# SODIMM.net
KiCad netlist of a schematic drawn in Altium Designer
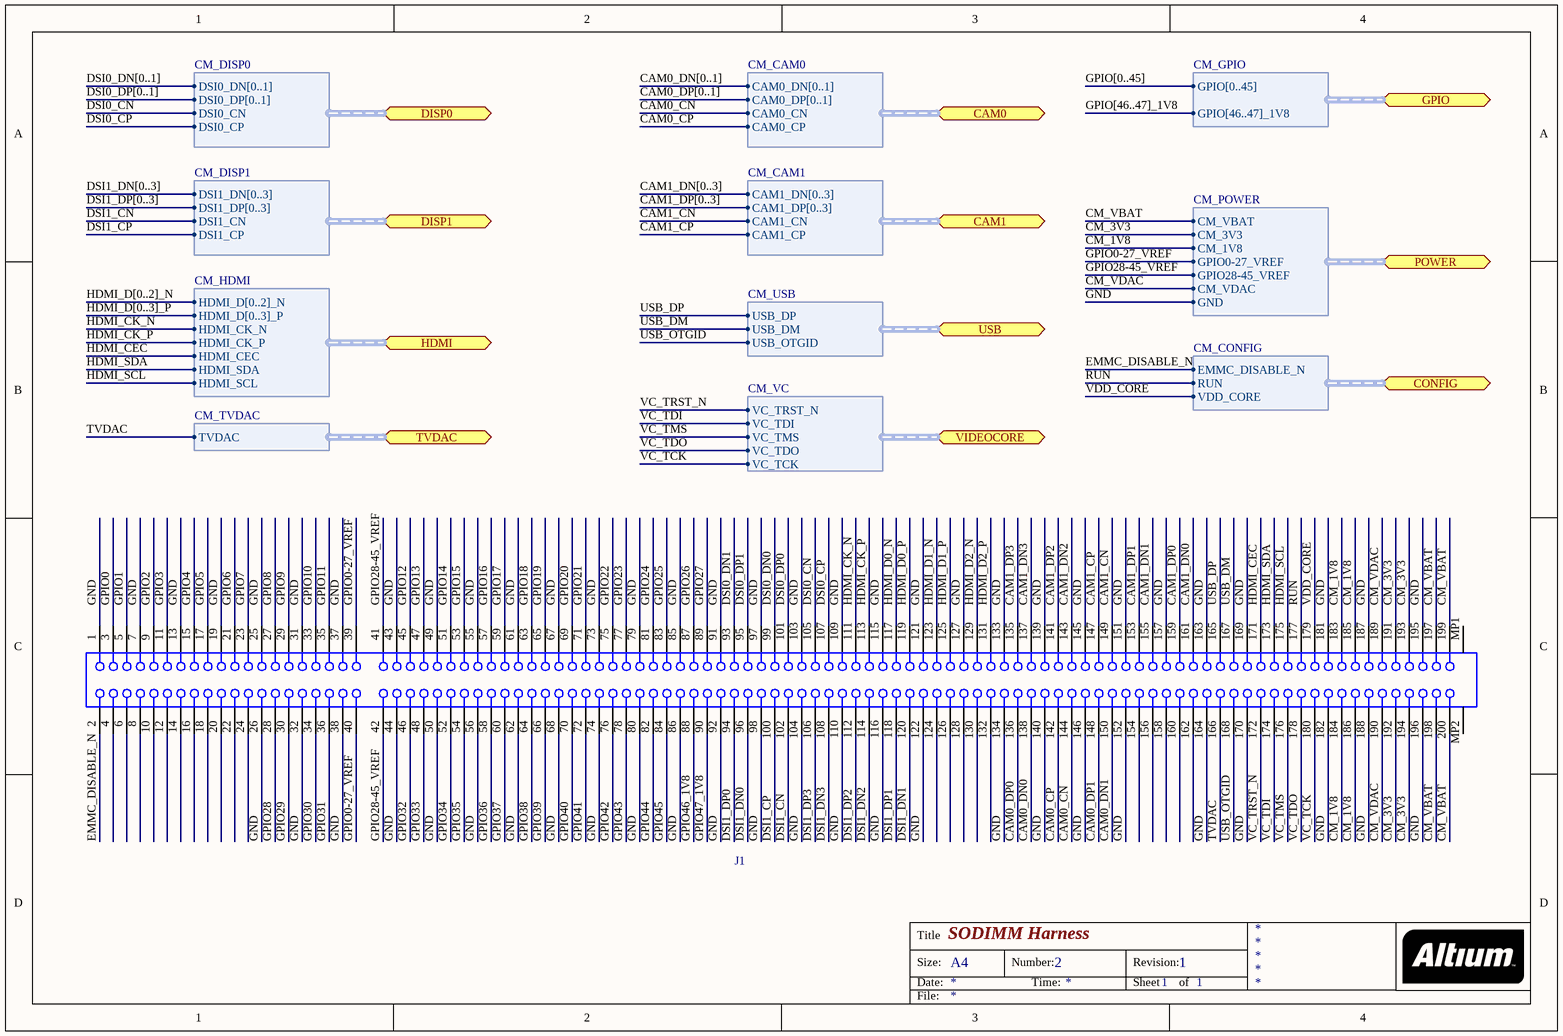
[diagram p0: SODIMM.SchDoc]

(export (version "E")
  (design (tool "Eeschema 10.0.6"))
  (components
    (comp (ref "J1")
      (value "~")
      (footprint "BTB-SM0-6-2V200")
      (description "Board-to-Board Connector, SMT, Vertical, Pitch 0.6mm, 200-Position")
      (fields (field (name "PUBLISHER") "Altium"))
      (libsource (lib "Altium Shanghai") (part "CMP-0001-00111-1"))
    )
  )
  (nets
    (net (code "15") (name "/CAM0_CN") (class "Default")
      (node (ref "J1") (pin "144") (pinfunction "144_144") (pintype "passive"))
    )
    (net (code "16") (name "/CAM0_CP") (class "Default")
      (node (ref "J1") (pin "142") (pinfunction "142_142") (pintype "passive"))
    )
    (net (code "17") (name "/CAM0_DN0") (class "Default")
      (node (ref "J1") (pin "138") (pinfunction "138_138") (pintype "passive"))
    )
    (net (code "18") (name "/CAM0_DN1") (class "Default")
      (node (ref "J1") (pin "150") (pinfunction "150_150") (pintype "passive"))
    )
    (net (code "20") (name "/CAM0_DP0") (class "Default")
      (node (ref "J1") (pin "136") (pinfunction "136_136") (pintype "passive"))
    )
    (net (code "21") (name "/CAM0_DP1") (class "Default")
      (node (ref "J1") (pin "148") (pinfunction "148_148") (pintype "passive"))
    )
    (net (code "23") (name "/CAM1_CN") (class "Default")
      (node (ref "J1") (pin "149") (pinfunction "149_149") (pintype "passive"))
    )
    (net (code "24") (name "/CAM1_CP") (class "Default")
      (node (ref "J1") (pin "147") (pinfunction "147_147") (pintype "passive"))
    )
    (net (code "25") (name "/CAM1_DN0") (class "Default")
      (node (ref "J1") (pin "161") (pinfunction "161_161") (pintype "passive"))
    )
    (net (code "26") (name "/CAM1_DN1") (class "Default")
      (node (ref "J1") (pin "155") (pinfunction "155_155") (pintype "passive"))
    )
    (net (code "27") (name "/CAM1_DN2") (class "Default")
      (node (ref "J1") (pin "143") (pinfunction "143_143") (pintype "passive"))
    )
    (net (code "28") (name "/CAM1_DN3") (class "Default")
      (node (ref "J1") (pin "137") (pinfunction "137_137") (pintype "passive"))
    )
    (net (code "30") (name "/CAM1_DP0") (class "Default")
      (node (ref "J1") (pin "159") (pinfunction "159_159") (pintype "passive"))
    )
    (net (code "31") (name "/CAM1_DP1") (class "Default")
      (node (ref "J1") (pin "153") (pinfunction "153_153") (pintype "passive"))
    )
    (net (code "32") (name "/CAM1_DP2") (class "Default")
      (node (ref "J1") (pin "141") (pinfunction "141_141") (pintype "passive"))
    )
    (net (code "33") (name "/CAM1_DP3") (class "Default")
      (node (ref "J1") (pin "135") (pinfunction "135_135") (pintype "passive"))
    )
    (net (code "35") (name "/CM_1V8") (class "Default")
      (node (ref "J1") (pin "183") (pinfunction "183_183") (pintype "passive"))
      (node (ref "J1") (pin "184") (pinfunction "184_184") (pintype "passive"))
      (node (ref "J1") (pin "185") (pinfunction "185_185") (pintype "passive"))
      (node (ref "J1") (pin "186") (pinfunction "186_186") (pintype "passive"))
    )
    (net (code "36") (name "/CM_3V3") (class "Default")
      (node (ref "J1") (pin "191") (pinfunction "191_191") (pintype "passive"))
      (node (ref "J1") (pin "192") (pinfunction "192_192") (pintype "passive"))
      (node (ref "J1") (pin "193") (pinfunction "193_193") (pintype "passive"))
      (node (ref "J1") (pin "194") (pinfunction "194_194") (pintype "passive"))
    )
    (net (code "37") (name "/CM_VBAT") (class "Default")
      (node (ref "J1") (pin "197") (pinfunction "197_197") (pintype "passive"))
      (node (ref "J1") (pin "198") (pinfunction "198_198") (pintype "passive"))
      (node (ref "J1") (pin "199") (pinfunction "199_199") (pintype "passive"))
      (node (ref "J1") (pin "200") (pinfunction "200_200") (pintype "passive"))
    )
    (net (code "38") (name "/CM_VDAC") (class "Default")
      (node (ref "J1") (pin "189") (pinfunction "189_189") (pintype "passive"))
      (node (ref "J1") (pin "190") (pinfunction "190_190") (pintype "passive"))
    )
    (net (code "39") (name "/DSI0_CN") (class "Default")
      (node (ref "J1") (pin "105") (pinfunction "105_105") (pintype "passive"))
    )
    (net (code "40") (name "/DSI0_CP") (class "Default")
      (node (ref "J1") (pin "107") (pinfunction "107_107") (pintype "passive"))
    )
    (net (code "41") (name "/DSI0_DN0") (class "Default")
      (node (ref "J1") (pin "99") (pinfunction "99_99") (pintype "passive"))
    )
    (net (code "42") (name "/DSI0_DN1") (class "Default")
      (node (ref "J1") (pin "93") (pinfunction "93_93") (pintype "passive"))
    )
    (net (code "44") (name "/DSI0_DP0") (class "Default")
      (node (ref "J1") (pin "101") (pinfunction "101_101") (pintype "passive"))
    )
    (net (code "45") (name "/DSI0_DP1") (class "Default")
      (node (ref "J1") (pin "95") (pinfunction "95_95") (pintype "passive"))
    )
    (net (code "47") (name "/DSI1_CN") (class "Default")
      (node (ref "J1") (pin "102") (pinfunction "102_102") (pintype "passive"))
    )
    (net (code "48") (name "/DSI1_CP") (class "Default")
      (node (ref "J1") (pin "100") (pinfunction "100_100") (pintype "passive"))
    )
    (net (code "49") (name "/DSI1_DN0") (class "Default")
      (node (ref "J1") (pin "96") (pinfunction "96_96") (pintype "passive"))
    )
    (net (code "50") (name "/DSI1_DN1") (class "Default")
      (node (ref "J1") (pin "120") (pinfunction "120_120") (pintype "passive"))
    )
    (net (code "51") (name "/DSI1_DN2") (class "Default")
      (node (ref "J1") (pin "114") (pinfunction "114_114") (pintype "passive"))
    )
    (net (code "52") (name "/DSI1_DN3") (class "Default")
      (node (ref "J1") (pin "108") (pinfunction "108_108") (pintype "passive"))
    )
    (net (code "54") (name "/DSI1_DP0") (class "Default")
      (node (ref "J1") (pin "94") (pinfunction "94_94") (pintype "passive"))
    )
    (net (code "55") (name "/DSI1_DP1") (class "Default")
      (node (ref "J1") (pin "118") (pinfunction "118_118") (pintype "passive"))
    )
    (net (code "56") (name "/DSI1_DP2") (class "Default")
      (node (ref "J1") (pin "112") (pinfunction "112_112") (pintype "passive"))
    )
    (net (code "57") (name "/DSI1_DP3") (class "Default")
      (node (ref "J1") (pin "106") (pinfunction "106_106") (pintype "passive"))
    )
    (net (code "59") (name "/EMMC_DISABLE_N") (class "Default")
      (node (ref "J1") (pin "2") (pinfunction "2_2") (pintype "passive"))
    )
    (net (code "60") (name "/GND") (class "Default")
      (node (ref "J1") (pin "1") (pinfunction "1_1") (pintype "passive"))
      (node (ref "J1") (pin "103") (pinfunction "103_103") (pintype "passive"))
      (node (ref "J1") (pin "104") (pinfunction "104_104") (pintype "passive"))
      (node (ref "J1") (pin "109") (pinfunction "109_109") (pintype "passive"))
      (node (ref "J1") (pin "110") (pinfunction "110_110") (pintype "passive"))
      (node (ref "J1") (pin "115") (pinfunction "115_115") (pintype "passive"))
      (node (ref "J1") (pin "116") (pinfunction "116_116") (pintype "passive"))
      (node (ref "J1") (pin "121") (pinfunction "121_121") (pintype "passive"))
      (node (ref "J1") (pin "122") (pinfunction "122_122") (pintype "passive"))
      (node (ref "J1") (pin "127") (pinfunction "127_127") (pintype "passive"))
      (node (ref "J1") (pin "13") (pinfunction "13_13") (pintype "passive"))
      (node (ref "J1") (pin "133") (pinfunction "133_133") (pintype "passive"))
      (node (ref "J1") (pin "134") (pinfunction "134_134") (pintype "passive"))
      (node (ref "J1") (pin "139") (pinfunction "139_139") (pintype "passive"))
      (node (ref "J1") (pin "140") (pinfunction "140_140") (pintype "passive"))
      (node (ref "J1") (pin "145") (pinfunction "145_145") (pintype "passive"))
      (node (ref "J1") (pin "146") (pinfunction "146_146") (pintype "passive"))
      (node (ref "J1") (pin "151") (pinfunction "151_151") (pintype "passive"))
      (node (ref "J1") (pin "152") (pinfunction "152_152") (pintype "passive"))
      (node (ref "J1") (pin "157") (pinfunction "157_157") (pintype "passive"))
      (node (ref "J1") (pin "163") (pinfunction "163_163") (pintype "passive"))
      (node (ref "J1") (pin "164") (pinfunction "164_164") (pintype "passive"))
      (node (ref "J1") (pin "169") (pinfunction "169_169") (pintype "passive"))
      (node (ref "J1") (pin "170") (pinfunction "170_170") (pintype "passive"))
      (node (ref "J1") (pin "181") (pinfunction "181_181") (pintype "passive"))
      (node (ref "J1") (pin "182") (pinfunction "182_182") (pintype "passive"))
      (node (ref "J1") (pin "187") (pinfunction "187_187") (pintype "passive"))
      (node (ref "J1") (pin "188") (pinfunction "188_188") (pintype "passive"))
      (node (ref "J1") (pin "19") (pinfunction "19_19") (pintype "passive"))
      (node (ref "J1") (pin "195") (pinfunction "195_195") (pintype "passive"))
      (node (ref "J1") (pin "196") (pinfunction "196_196") (pintype "passive"))
      (node (ref "J1") (pin "25") (pinfunction "25_25") (pintype "passive"))
      (node (ref "J1") (pin "26") (pinfunction "26_26") (pintype "passive"))
      (node (ref "J1") (pin "31") (pinfunction "31_31") (pintype "passive"))
      (node (ref "J1") (pin "32") (pinfunction "32_32") (pintype "passive"))
      (node (ref "J1") (pin "37") (pinfunction "37_37") (pintype "passive"))
      (node (ref "J1") (pin "38") (pinfunction "38_38") (pintype "passive"))
      (node (ref "J1") (pin "43") (pinfunction "43_43") (pintype "passive"))
      (node (ref "J1") (pin "44") (pinfunction "44_44") (pintype "passive"))
      (node (ref "J1") (pin "49") (pinfunction "49_49") (pintype "passive"))
      (node (ref "J1") (pin "50") (pinfunction "50_50") (pintype "passive"))
      (node (ref "J1") (pin "55") (pinfunction "55_55") (pintype "passive"))
      (node (ref "J1") (pin "56") (pinfunction "56_56") (pintype "passive"))
      (node (ref "J1") (pin "61") (pinfunction "61_61") (pintype "passive"))
      (node (ref "J1") (pin "62") (pinfunction "62_62") (pintype "passive"))
      (node (ref "J1") (pin "67") (pinfunction "67_67") (pintype "passive"))
      (node (ref "J1") (pin "68") (pinfunction "68_68") (pintype "passive"))
      (node (ref "J1") (pin "7") (pinfunction "7_7") (pintype "passive"))
      (node (ref "J1") (pin "73") (pinfunction "73_73") (pintype "passive"))
      (node (ref "J1") (pin "74") (pinfunction "74_74") (pintype "passive"))
      (node (ref "J1") (pin "79") (pinfunction "79_79") (pintype "passive"))
      (node (ref "J1") (pin "80") (pinfunction "80_80") (pintype "passive"))
      (node (ref "J1") (pin "85") (pinfunction "85_85") (pintype "passive"))
      (node (ref "J1") (pin "86") (pinfunction "86_86") (pintype "passive"))
      (node (ref "J1") (pin "91") (pinfunction "91_91") (pintype "passive"))
      (node (ref "J1") (pin "92") (pinfunction "92_92") (pintype "passive"))
      (node (ref "J1") (pin "97") (pinfunction "97_97") (pintype "passive"))
      (node (ref "J1") (pin "98") (pinfunction "98_98") (pintype "passive"))
    )
    (net (code "61") (name "/GPIO0") (class "Default")
      (node (ref "J1") (pin "3") (pinfunction "3_3") (pintype "passive"))
    )
    (net (code "62") (name "/GPIO0-27_VREF") (class "Default")
      (node (ref "J1") (pin "39") (pinfunction "39_39") (pintype "passive"))
      (node (ref "J1") (pin "40") (pinfunction "40_40") (pintype "passive"))
    )
    (net (code "63") (name "/GPIO1") (class "Default")
      (node (ref "J1") (pin "5") (pinfunction "5_5") (pintype "passive"))
    )
    (net (code "64") (name "/GPIO2") (class "Default")
      (node (ref "J1") (pin "9") (pinfunction "9_9") (pintype "passive"))
    )
    (net (code "65") (name "/GPIO3") (class "Default")
      (node (ref "J1") (pin "11") (pinfunction "11_11") (pintype "passive"))
    )
    (net (code "66") (name "/GPIO4") (class "Default")
      (node (ref "J1") (pin "15") (pinfunction "15_15") (pintype "passive"))
    )
    (net (code "67") (name "/GPIO5") (class "Default")
      (node (ref "J1") (pin "17") (pinfunction "17_17") (pintype "passive"))
    )
    (net (code "68") (name "/GPIO6") (class "Default")
      (node (ref "J1") (pin "21") (pinfunction "21_21") (pintype "passive"))
    )
    (net (code "69") (name "/GPIO7") (class "Default")
      (node (ref "J1") (pin "23") (pinfunction "23_23") (pintype "passive"))
    )
    (net (code "70") (name "/GPIO8") (class "Default")
      (node (ref "J1") (pin "27") (pinfunction "27_27") (pintype "passive"))
    )
    (net (code "71") (name "/GPIO9") (class "Default")
      (node (ref "J1") (pin "29") (pinfunction "29_29") (pintype "passive"))
    )
    (net (code "72") (name "/GPIO10") (class "Default")
      (node (ref "J1") (pin "33") (pinfunction "33_33") (pintype "passive"))
    )
    (net (code "73") (name "/GPIO11") (class "Default")
      (node (ref "J1") (pin "35") (pinfunction "35_35") (pintype "passive"))
    )
    (net (code "74") (name "/GPIO12") (class "Default")
      (node (ref "J1") (pin "45") (pinfunction "45_45") (pintype "passive"))
    )
    (net (code "75") (name "/GPIO13") (class "Default")
      (node (ref "J1") (pin "47") (pinfunction "47_47") (pintype "passive"))
    )
    (net (code "76") (name "/GPIO14") (class "Default")
      (node (ref "J1") (pin "51") (pinfunction "51_51") (pintype "passive"))
    )
    (net (code "77") (name "/GPIO15") (class "Default")
      (node (ref "J1") (pin "53") (pinfunction "53_53") (pintype "passive"))
    )
    (net (code "78") (name "/GPIO16") (class "Default")
      (node (ref "J1") (pin "57") (pinfunction "57_57") (pintype "passive"))
    )
    (net (code "79") (name "/GPIO17") (class "Default")
      (node (ref "J1") (pin "59") (pinfunction "59_59") (pintype "passive"))
    )
    (net (code "80") (name "/GPIO18") (class "Default")
      (node (ref "J1") (pin "63") (pinfunction "63_63") (pintype "passive"))
    )
    (net (code "81") (name "/GPIO19") (class "Default")
      (node (ref "J1") (pin "65") (pinfunction "65_65") (pintype "passive"))
    )
    (net (code "82") (name "/GPIO20") (class "Default")
      (node (ref "J1") (pin "69") (pinfunction "69_69") (pintype "passive"))
    )
    (net (code "83") (name "/GPIO21") (class "Default")
      (node (ref "J1") (pin "71") (pinfunction "71_71") (pintype "passive"))
    )
    (net (code "84") (name "/GPIO22") (class "Default")
      (node (ref "J1") (pin "75") (pinfunction "75_75") (pintype "passive"))
    )
    (net (code "85") (name "/GPIO23") (class "Default")
      (node (ref "J1") (pin "77") (pinfunction "77_77") (pintype "passive"))
    )
    (net (code "86") (name "/GPIO24") (class "Default")
      (node (ref "J1") (pin "81") (pinfunction "81_81") (pintype "passive"))
    )
    (net (code "87") (name "/GPIO25") (class "Default")
      (node (ref "J1") (pin "83") (pinfunction "83_83") (pintype "passive"))
    )
    (net (code "88") (name "/GPIO26") (class "Default")
      (node (ref "J1") (pin "87") (pinfunction "87_87") (pintype "passive"))
    )
    (net (code "89") (name "/GPIO27") (class "Default")
      (node (ref "J1") (pin "89") (pinfunction "89_89") (pintype "passive"))
    )
    (net (code "90") (name "/GPIO28") (class "Default")
      (node (ref "J1") (pin "28") (pinfunction "28_28") (pintype "passive"))
    )
    (net (code "91") (name "/GPIO28-45_VREF") (class "Default")
      (node (ref "J1") (pin "41") (pinfunction "41_41") (pintype "passive"))
      (node (ref "J1") (pin "42") (pinfunction "42_42") (pintype "passive"))
    )
    (net (code "92") (name "/GPIO29") (class "Default")
      (node (ref "J1") (pin "30") (pinfunction "30_30") (pintype "passive"))
    )
    (net (code "93") (name "/GPIO30") (class "Default")
      (node (ref "J1") (pin "34") (pinfunction "34_34") (pintype "passive"))
    )
    (net (code "94") (name "/GPIO31") (class "Default")
      (node (ref "J1") (pin "36") (pinfunction "36_36") (pintype "passive"))
    )
    (net (code "95") (name "/GPIO32") (class "Default")
      (node (ref "J1") (pin "46") (pinfunction "46_46") (pintype "passive"))
    )
    (net (code "96") (name "/GPIO33") (class "Default")
      (node (ref "J1") (pin "48") (pinfunction "48_48") (pintype "passive"))
    )
    (net (code "97") (name "/GPIO34") (class "Default")
      (node (ref "J1") (pin "52") (pinfunction "52_52") (pintype "passive"))
    )
    (net (code "98") (name "/GPIO35") (class "Default")
      (node (ref "J1") (pin "54") (pinfunction "54_54") (pintype "passive"))
    )
    (net (code "99") (name "/GPIO36") (class "Default")
      (node (ref "J1") (pin "58") (pinfunction "58_58") (pintype "passive"))
    )
    (net (code "100") (name "/GPIO37") (class "Default")
      (node (ref "J1") (pin "60") (pinfunction "60_60") (pintype "passive"))
    )
    (net (code "101") (name "/GPIO38") (class "Default")
      (node (ref "J1") (pin "64") (pinfunction "64_64") (pintype "passive"))
    )
    (net (code "102") (name "/GPIO39") (class "Default")
      (node (ref "J1") (pin "66") (pinfunction "66_66") (pintype "passive"))
    )
    (net (code "103") (name "/GPIO40") (class "Default")
      (node (ref "J1") (pin "70") (pinfunction "70_70") (pintype "passive"))
    )
    (net (code "104") (name "/GPIO41") (class "Default")
      (node (ref "J1") (pin "72") (pinfunction "72_72") (pintype "passive"))
    )
    (net (code "105") (name "/GPIO42") (class "Default")
      (node (ref "J1") (pin "76") (pinfunction "76_76") (pintype "passive"))
    )
    (net (code "106") (name "/GPIO43") (class "Default")
      (node (ref "J1") (pin "78") (pinfunction "78_78") (pintype "passive"))
    )
    (net (code "107") (name "/GPIO44") (class "Default")
      (node (ref "J1") (pin "82") (pinfunction "82_82") (pintype "passive"))
    )
    (net (code "108") (name "/GPIO45") (class "Default")
      (node (ref "J1") (pin "84") (pinfunction "84_84") (pintype "passive"))
    )
    (net (code "109") (name "/GPIO46_1V8") (class "Default")
      (node (ref "J1") (pin "88") (pinfunction "88_88") (pintype "passive"))
    )
    (net (code "110") (name "/GPIO47_1V8") (class "Default")
      (node (ref "J1") (pin "90") (pinfunction "90_90") (pintype "passive"))
    )
    (net (code "112") (name "/HDMI_CEC") (class "Default")
      (node (ref "J1") (pin "171") (pinfunction "171_171") (pintype "passive"))
    )
    (net (code "113") (name "/HDMI_CK_N") (class "Default")
      (node (ref "J1") (pin "111") (pinfunction "111_111") (pintype "passive"))
    )
    (net (code "114") (name "/HDMI_CK_P") (class "Default")
      (node (ref "J1") (pin "113") (pinfunction "113_113") (pintype "passive"))
    )
    (net (code "115") (name "/HDMI_D0_N") (class "Default")
      (node (ref "J1") (pin "117") (pinfunction "117_117") (pintype "passive"))
    )
    (net (code "116") (name "/HDMI_D0_P") (class "Default")
      (node (ref "J1") (pin "119") (pinfunction "119_119") (pintype "passive"))
    )
    (net (code "117") (name "/HDMI_D1_N") (class "Default")
      (node (ref "J1") (pin "123") (pinfunction "123_123") (pintype "passive"))
    )
    (net (code "118") (name "/HDMI_D1_P") (class "Default")
      (node (ref "J1") (pin "125") (pinfunction "125_125") (pintype "passive"))
    )
    (net (code "119") (name "/HDMI_D2_N") (class "Default")
      (node (ref "J1") (pin "129") (pinfunction "129_129") (pintype "passive"))
    )
    (net (code "120") (name "/HDMI_D2_P") (class "Default")
      (node (ref "J1") (pin "131") (pinfunction "131_131") (pintype "passive"))
    )
    (net (code "121") (name "/HDMI_SCL") (class "Default")
      (node (ref "J1") (pin "175") (pinfunction "175_175") (pintype "passive"))
    )
    (net (code "122") (name "/HDMI_SDA") (class "Default")
      (node (ref "J1") (pin "173") (pinfunction "173_173") (pintype "passive"))
    )
    (net (code "123") (name "/RUN") (class "Default")
      (node (ref "J1") (pin "177") (pinfunction "177_177") (pintype "passive"))
    )
    (net (code "124") (name "/TVDAC") (class "Default")
      (node (ref "J1") (pin "166") (pinfunction "166_166") (pintype "passive"))
    )
    (net (code "125") (name "/USB_DM") (class "Default")
      (node (ref "J1") (pin "167") (pinfunction "167_167") (pintype "passive"))
    )
    (net (code "126") (name "/USB_DP") (class "Default")
      (node (ref "J1") (pin "165") (pinfunction "165_165") (pintype "passive"))
    )
    (net (code "127") (name "/USB_OTGID") (class "Default")
      (node (ref "J1") (pin "168") (pinfunction "168_168") (pintype "passive"))
    )
    (net (code "128") (name "/VC_TCK") (class "Default")
      (node (ref "J1") (pin "180") (pinfunction "180_180") (pintype "passive"))
    )
    (net (code "129") (name "/VC_TDI") (class "Default")
      (node (ref "J1") (pin "174") (pinfunction "174_174") (pintype "passive"))
    )
    (net (code "130") (name "/VC_TDO") (class "Default")
      (node (ref "J1") (pin "178") (pinfunction "178_178") (pintype "passive"))
    )
    (net (code "131") (name "/VC_TMS") (class "Default")
      (node (ref "J1") (pin "176") (pinfunction "176_176") (pintype "passive"))
    )
    (net (code "132") (name "/VC_TRST_N") (class "Default")
      (node (ref "J1") (pin "172") (pinfunction "172_172") (pintype "passive"))
    )
    (net (code "133") (name "/VDD_CORE") (class "Default")
      (node (ref "J1") (pin "179") (pinfunction "179_179") (pintype "passive"))
    )
    (net (code "148") (name "unconnected-(J1-Pad4)") (class "Default")
      (node (ref "J1") (pin "4") (pinfunction "4_4") (pintype "passive"))
    )
    (net (code "149") (name "unconnected-(J1-Pad6)") (class "Default")
      (node (ref "J1") (pin "6") (pinfunction "6_6") (pintype "passive"))
    )
    (net (code "150") (name "unconnected-(J1-Pad8)") (class "Default")
      (node (ref "J1") (pin "8") (pinfunction "8_8") (pintype "passive"))
    )
    (net (code "151") (name "unconnected-(J1-Pad10)") (class "Default")
      (node (ref "J1") (pin "10") (pinfunction "10_10") (pintype "passive"))
    )
    (net (code "152") (name "unconnected-(J1-Pad12)") (class "Default")
      (node (ref "J1") (pin "12") (pinfunction "12_12") (pintype "passive"))
    )
    (net (code "153") (name "unconnected-(J1-Pad14)") (class "Default")
      (node (ref "J1") (pin "14") (pinfunction "14_14") (pintype "passive"))
    )
    (net (code "154") (name "unconnected-(J1-Pad16)") (class "Default")
      (node (ref "J1") (pin "16") (pinfunction "16_16") (pintype "passive"))
    )
    (net (code "155") (name "unconnected-(J1-Pad18)") (class "Default")
      (node (ref "J1") (pin "18") (pinfunction "18_18") (pintype "passive"))
    )
    (net (code "156") (name "unconnected-(J1-Pad20)") (class "Default")
      (node (ref "J1") (pin "20") (pinfunction "20_20") (pintype "passive"))
    )
    (net (code "157") (name "unconnected-(J1-Pad22)") (class "Default")
      (node (ref "J1") (pin "22") (pinfunction "22_22") (pintype "passive"))
    )
    (net (code "158") (name "unconnected-(J1-Pad24)") (class "Default")
      (node (ref "J1") (pin "24") (pinfunction "24_24") (pintype "passive"))
    )
    (net (code "159") (name "unconnected-(J1-Pad124)") (class "Default")
      (node (ref "J1") (pin "124") (pinfunction "124_124") (pintype "passive"))
    )
    (net (code "160") (name "unconnected-(J1-Pad126)") (class "Default")
      (node (ref "J1") (pin "126") (pinfunction "126_126") (pintype "passive"))
    )
    (net (code "161") (name "unconnected-(J1-Pad128)") (class "Default")
      (node (ref "J1") (pin "128") (pinfunction "128_128") (pintype "passive"))
    )
    (net (code "162") (name "unconnected-(J1-Pad130)") (class "Default")
      (node (ref "J1") (pin "130") (pinfunction "130_130") (pintype "passive"))
    )
    (net (code "163") (name "unconnected-(J1-Pad132)") (class "Default")
      (node (ref "J1") (pin "132") (pinfunction "132_132") (pintype "passive"))
    )
    (net (code "164") (name "unconnected-(J1-Pad154)") (class "Default")
      (node (ref "J1") (pin "154") (pinfunction "154_154") (pintype "passive"))
    )
    (net (code "165") (name "unconnected-(J1-Pad156)") (class "Default")
      (node (ref "J1") (pin "156") (pinfunction "156_156") (pintype "passive"))
    )
    (net (code "166") (name "unconnected-(J1-Pad158)") (class "Default")
      (node (ref "J1") (pin "158") (pinfunction "158_158") (pintype "passive"))
    )
    (net (code "167") (name "unconnected-(J1-Pad160)") (class "Default")
      (node (ref "J1") (pin "160") (pinfunction "160_160") (pintype "passive"))
    )
    (net (code "168") (name "unconnected-(J1-Pad162)") (class "Default")
      (node (ref "J1") (pin "162") (pinfunction "162_162") (pintype "passive"))
    )
    (net (code "169") (name "unconnected-(J1-PadMP1)") (class "Default")
      (node (ref "J1") (pin "MP1") (pinfunction "MP1_MP1") (pintype "passive"))
    )
    (net (code "170") (name "unconnected-(J1-PadMP2)") (class "Default")
      (node (ref "J1") (pin "MP2") (pinfunction "MP2_MP2") (pintype "passive"))
    )
  )
)
